# proto.net
KiCad netlist of a schematic drawn in EAGLE
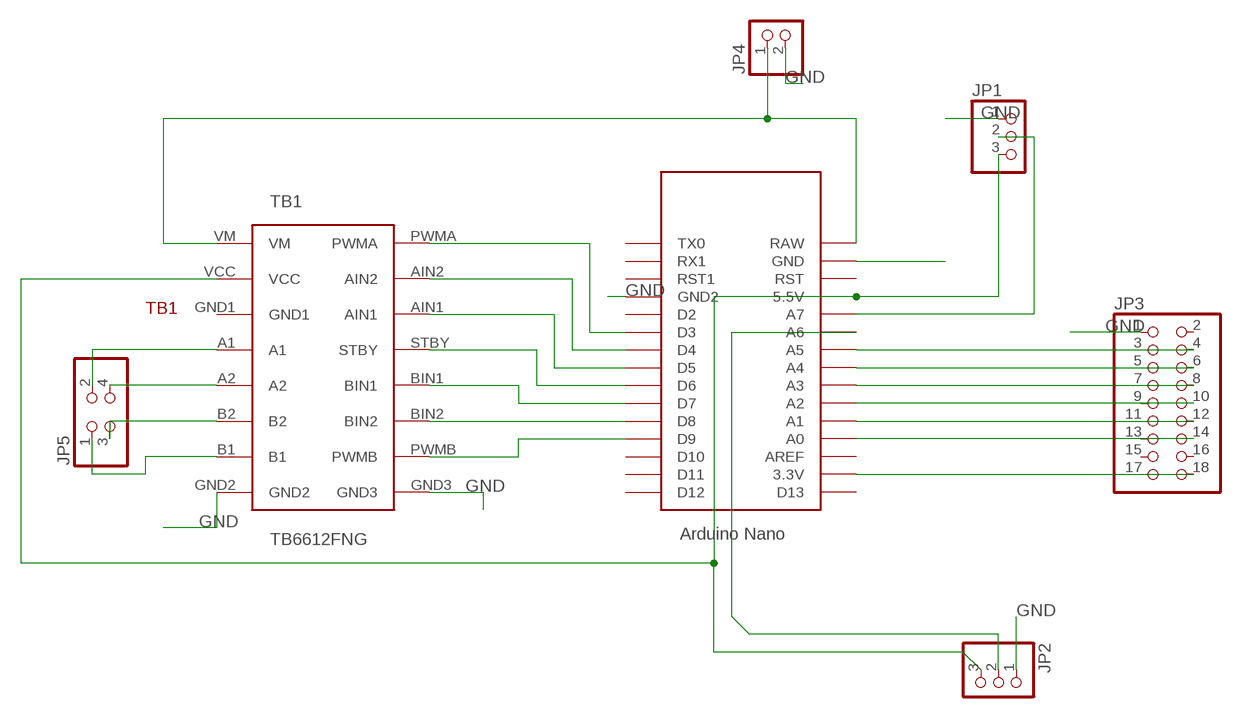
[diagram p0: schematic, sheet 1]

(export (version "E")
  (design (tool "Eeschema 10.0.6"))
  (components
    (comp (ref "JP1")
      (value "PINHD-1X3")
      (footprint "eagle-import:1X03")
      (libsource (lib "eagle-import") (part "PINHD-1X3"))
    )
    (comp (ref "JP2")
      (value "PINHD-1X3")
      (footprint "eagle-import:1X03")
      (libsource (lib "eagle-import") (part "PINHD-1X3"))
    )
    (comp (ref "JP3")
      (value "PINHD-2X9")
      (footprint "eagle-import:2X09")
      (libsource (lib "eagle-import") (part "PINHD-2X9"))
    )
    (comp (ref "JP4")
      (value "PINHD-1X2")
      (footprint "eagle-import:1X02")
      (libsource (lib "eagle-import") (part "PINHD-1X2"))
    )
    (comp (ref "JP5")
      (value "PINHD-2X2")
      (footprint "eagle-import:2X02")
      (libsource (lib "eagle-import") (part "PINHD-2X2"))
    )
    (comp (ref "TB1")
      (value "TB6612FNG")
      (footprint "eagle-import:TB6612FNG")
      (libsource (lib "eagle-import") (part "TB6612FNG"))
    )
    (comp (ref "U$1")
      (value "NANO")
      (footprint "eagle-import:NANO")
      (libsource (lib "eagle-import") (part "NANO"))
    )
  )
  (nets
    (net (code "1") (name "/GND") (class "Default")
      (node (ref "JP1") (pin "1") (pinfunction "1_1") (pintype "passive"))
      (node (ref "JP2") (pin "1") (pinfunction "1_1") (pintype "passive"))
      (node (ref "JP3") (pin "1") (pinfunction "1_1") (pintype "passive"))
      (node (ref "JP4") (pin "2") (pinfunction "2_2") (pintype "passive"))
      (node (ref "TB1") (pin "GND2") (pinfunction "GND2_GND2") (pintype "bidirectional"))
      (node (ref "TB1") (pin "GND3") (pinfunction "GND3_GND3") (pintype "bidirectional"))
      (node (ref "U$1") (pin "GND") (pinfunction "GND_GND") (pintype "bidirectional"))
      (node (ref "U$1") (pin "GND1") (pinfunction "GND2_GND1") (pintype "bidirectional"))
    )
    (net (code "2") (name "Net-(JP1-Pad2)") (class "Default")
      (node (ref "JP1") (pin "2") (pinfunction "2_2") (pintype "passive"))
      (node (ref "U$1") (pin "A7") (pinfunction "A7_A7") (pintype "bidirectional"))
    )
    (net (code "3") (name "Net-(JP2-Pad2)") (class "Default")
      (node (ref "JP2") (pin "2") (pinfunction "2_2") (pintype "passive"))
      (node (ref "U$1") (pin "A6") (pinfunction "A6_A6") (pintype "bidirectional"))
    )
    (net (code "4") (name "Net-(JP3-Pad4)") (class "Default")
      (node (ref "JP3") (pin "4") (pinfunction "4_4") (pintype "passive"))
      (node (ref "U$1") (pin "A5") (pinfunction "A5_A5") (pintype "bidirectional"))
    )
    (net (code "5") (name "Net-(JP3-Pad6)") (class "Default")
      (node (ref "JP3") (pin "6") (pinfunction "6_6") (pintype "passive"))
      (node (ref "U$1") (pin "A4") (pinfunction "A4_A4") (pintype "bidirectional"))
    )
    (net (code "6") (name "Net-(JP3-Pad8)") (class "Default")
      (node (ref "JP3") (pin "8") (pinfunction "8_8") (pintype "passive"))
      (node (ref "U$1") (pin "A3") (pinfunction "A3_A3") (pintype "bidirectional"))
    )
    (net (code "7") (name "Net-(JP3-Pad10)") (class "Default")
      (node (ref "JP3") (pin "10") (pinfunction "10_10") (pintype "passive"))
      (node (ref "U$1") (pin "A2") (pinfunction "A2_A2") (pintype "bidirectional"))
    )
    (net (code "8") (name "Net-(JP3-Pad12)") (class "Default")
      (node (ref "JP3") (pin "12") (pinfunction "12_12") (pintype "passive"))
      (node (ref "U$1") (pin "A1") (pinfunction "A1_A1") (pintype "bidirectional"))
    )
    (net (code "9") (name "Net-(JP3-Pad14)") (class "Default")
      (node (ref "JP3") (pin "14") (pinfunction "14_14") (pintype "passive"))
      (node (ref "U$1") (pin "A0") (pinfunction "A0_A0") (pintype "bidirectional"))
    )
    (net (code "10") (name "Net-(JP3-Pad18)") (class "Default")
      (node (ref "JP3") (pin "18") (pinfunction "18_18") (pintype "passive"))
      (node (ref "U$1") (pin "3.3V") (pinfunction "3.3V_3.3V") (pintype "bidirectional"))
    )
    (net (code "11") (name "Net-(JP4-Pad1)") (class "Default")
      (node (ref "JP4") (pin "1") (pinfunction "1_1") (pintype "passive"))
      (node (ref "TB1") (pin "VM") (pinfunction "VM_VM") (pintype "bidirectional"))
      (node (ref "U$1") (pin "RAW") (pinfunction "RAW_RAW") (pintype "bidirectional"))
    )
    (net (code "12") (name "Net-(JP5-Pad1)") (class "Default")
      (node (ref "JP5") (pin "1") (pinfunction "1_1") (pintype "passive"))
      (node (ref "TB1") (pin "B1") (pinfunction "B1_B1") (pintype "bidirectional"))
    )
    (net (code "13") (name "Net-(JP5-Pad2)") (class "Default")
      (node (ref "JP5") (pin "2") (pinfunction "2_2") (pintype "passive"))
      (node (ref "TB1") (pin "A1") (pinfunction "A1_A1") (pintype "bidirectional"))
    )
    (net (code "14") (name "Net-(JP5-Pad3)") (class "Default")
      (node (ref "JP5") (pin "3") (pinfunction "3_3") (pintype "passive"))
      (node (ref "TB1") (pin "B2") (pinfunction "B2_B2") (pintype "bidirectional"))
    )
    (net (code "15") (name "Net-(JP5-Pad4)") (class "Default")
      (node (ref "JP5") (pin "4") (pinfunction "4_4") (pintype "passive"))
      (node (ref "TB1") (pin "A2") (pinfunction "A2_A2") (pintype "bidirectional"))
    )
    (net (code "16") (name "Net-(TB1-PadAIN1)") (class "Default")
      (node (ref "TB1") (pin "AIN1") (pinfunction "AIN1_AIN1") (pintype "bidirectional"))
      (node (ref "U$1") (pin "D5") (pinfunction "D5_D5") (pintype "bidirectional"))
    )
    (net (code "17") (name "Net-(TB1-PadAIN2)") (class "Default")
      (node (ref "TB1") (pin "AIN2") (pinfunction "AIN2_AIN2") (pintype "bidirectional"))
      (node (ref "U$1") (pin "D4") (pinfunction "D4_D4") (pintype "bidirectional"))
    )
    (net (code "18") (name "Net-(TB1-PadBIN1)") (class "Default")
      (node (ref "TB1") (pin "BIN1") (pinfunction "BIN1_BIN1") (pintype "bidirectional"))
      (node (ref "U$1") (pin "D7") (pinfunction "D7_D7") (pintype "bidirectional"))
    )
    (net (code "19") (name "Net-(TB1-PadBIN2)") (class "Default")
      (node (ref "TB1") (pin "BIN2") (pinfunction "BIN2_BIN2") (pintype "bidirectional"))
      (node (ref "U$1") (pin "D8") (pinfunction "D8_D8") (pintype "bidirectional"))
    )
    (net (code "20") (name "Net-(TB1-PadPWMA)") (class "Default")
      (node (ref "TB1") (pin "PWMA") (pinfunction "PWMA_PWMA") (pintype "bidirectional"))
      (node (ref "U$1") (pin "D3") (pinfunction "D3_D3") (pintype "bidirectional"))
    )
    (net (code "21") (name "Net-(TB1-PadPWMB)") (class "Default")
      (node (ref "TB1") (pin "PWMB") (pinfunction "PWMB_PWMB") (pintype "bidirectional"))
      (node (ref "U$1") (pin "D9") (pinfunction "D9_D9") (pintype "bidirectional"))
    )
    (net (code "22") (name "Net-(TB1-PadSTBY)") (class "Default")
      (node (ref "TB1") (pin "STBY") (pinfunction "STBY_STBY") (pintype "bidirectional"))
      (node (ref "U$1") (pin "D6") (pinfunction "D6_D6") (pintype "bidirectional"))
    )
    (net (code "23") (name "Net-(U$1-5.5V)") (class "Default")
      (node (ref "JP1") (pin "3") (pinfunction "3_3") (pintype "passive"))
      (node (ref "JP2") (pin "3") (pinfunction "3_3") (pintype "passive"))
      (node (ref "TB1") (pin "VCC") (pinfunction "VCC_VCC") (pintype "bidirectional"))
      (node (ref "U$1") (pin "5V") (pinfunction "5.5V_5V") (pintype "bidirectional"))
    )
    (net (code "24") (name "unconnected-(JP3-Pad2)") (class "Default")
      (node (ref "JP3") (pin "2") (pinfunction "2_2") (pintype "passive"))
    )
    (net (code "25") (name "unconnected-(JP3-Pad3)") (class "Default")
      (node (ref "JP3") (pin "3") (pinfunction "3_3") (pintype "passive"))
    )
    (net (code "26") (name "unconnected-(JP3-Pad5)") (class "Default")
      (node (ref "JP3") (pin "5") (pinfunction "5_5") (pintype "passive"))
    )
    (net (code "27") (name "unconnected-(JP3-Pad7)") (class "Default")
      (node (ref "JP3") (pin "7") (pinfunction "7_7") (pintype "passive"))
    )
    (net (code "28") (name "unconnected-(JP3-Pad9)") (class "Default")
      (node (ref "JP3") (pin "9") (pinfunction "9_9") (pintype "passive"))
    )
    (net (code "29") (name "unconnected-(JP3-Pad11)") (class "Default")
      (node (ref "JP3") (pin "11") (pinfunction "11_11") (pintype "passive"))
    )
    (net (code "30") (name "unconnected-(JP3-Pad13)") (class "Default")
      (node (ref "JP3") (pin "13") (pinfunction "13_13") (pintype "passive"))
    )
    (net (code "31") (name "unconnected-(JP3-Pad15)") (class "Default")
      (node (ref "JP3") (pin "15") (pinfunction "15_15") (pintype "passive"))
    )
    (net (code "32") (name "unconnected-(JP3-Pad16)") (class "Default")
      (node (ref "JP3") (pin "16") (pinfunction "16_16") (pintype "passive"))
    )
    (net (code "33") (name "unconnected-(JP3-Pad17)") (class "Default")
      (node (ref "JP3") (pin "17") (pinfunction "17_17") (pintype "passive"))
    )
    (net (code "34") (name "unconnected-(TB1-PadGND1)") (class "Default")
      (node (ref "TB1") (pin "GND1") (pinfunction "GND1_GND1") (pintype "bidirectional"))
    )
    (net (code "35") (name "unconnected-(U$1-PadAREF)") (class "Default")
      (node (ref "U$1") (pin "AREF") (pinfunction "AREF_AREF") (pintype "bidirectional"))
    )
    (net (code "36") (name "unconnected-(U$1-PadD2)") (class "Default")
      (node (ref "U$1") (pin "D2") (pinfunction "D2_D2") (pintype "bidirectional"))
    )
    (net (code "37") (name "unconnected-(U$1-PadD10)") (class "Default")
      (node (ref "U$1") (pin "D10") (pinfunction "D10_D10") (pintype "bidirectional"))
    )
    (net (code "38") (name "unconnected-(U$1-PadD11)") (class "Default")
      (node (ref "U$1") (pin "D11") (pinfunction "D11_D11") (pintype "bidirectional"))
    )
    (net (code "39") (name "unconnected-(U$1-PadD12)") (class "Default")
      (node (ref "U$1") (pin "D12") (pinfunction "D12_D12") (pintype "bidirectional"))
    )
    (net (code "40") (name "unconnected-(U$1-PadD13)") (class "Default")
      (node (ref "U$1") (pin "D13") (pinfunction "D13_D13") (pintype "bidirectional"))
    )
    (net (code "41") (name "unconnected-(U$1-PadICSP1)") (class "Default")
      (node (ref "U$1") (pin "ICSP1") (pinfunction "ICSP1_ICSP1") (pintype "bidirectional"))
    )
    (net (code "42") (name "unconnected-(U$1-PadICSP2)") (class "Default")
      (node (ref "U$1") (pin "ICSP2") (pinfunction "ICSP2_ICSP2") (pintype "bidirectional"))
    )
    (net (code "43") (name "unconnected-(U$1-PadICSP3)") (class "Default")
      (node (ref "U$1") (pin "ICSP3") (pinfunction "ICSP3_ICSP3") (pintype "bidirectional"))
    )
    (net (code "44") (name "unconnected-(U$1-PadICSP4)") (class "Default")
      (node (ref "U$1") (pin "ICSP4") (pinfunction "ICSP4_ICSP4") (pintype "bidirectional"))
    )
    (net (code "45") (name "unconnected-(U$1-PadICSP5)") (class "Default")
      (node (ref "U$1") (pin "ICSP5") (pinfunction "ICSP5_ICSP5") (pintype "bidirectional"))
    )
    (net (code "46") (name "unconnected-(U$1-PadICSP6)") (class "Default")
      (node (ref "U$1") (pin "ICSP6") (pinfunction "ICSP6_ICSP6") (pintype "bidirectional"))
    )
    (net (code "47") (name "unconnected-(U$1-PadRST)") (class "Default")
      (node (ref "U$1") (pin "RST") (pinfunction "RST_RST") (pintype "bidirectional"))
    )
    (net (code "48") (name "unconnected-(U$1-PadRST1)") (class "Default")
      (node (ref "U$1") (pin "RST1") (pinfunction "RST1_RST1") (pintype "bidirectional"))
    )
    (net (code "49") (name "unconnected-(U$1-PadRX1)") (class "Default")
      (node (ref "U$1") (pin "RX1") (pinfunction "RX1_RX1") (pintype "bidirectional"))
    )
    (net (code "50") (name "unconnected-(U$1-PadTX0)") (class "Default")
      (node (ref "U$1") (pin "TX0") (pinfunction "TX0_TX0") (pintype "bidirectional"))
    )
  )
)
